# PortiloopV2Altium_Sch.net
KiCad netlist of a schematic drawn in Altium Designer
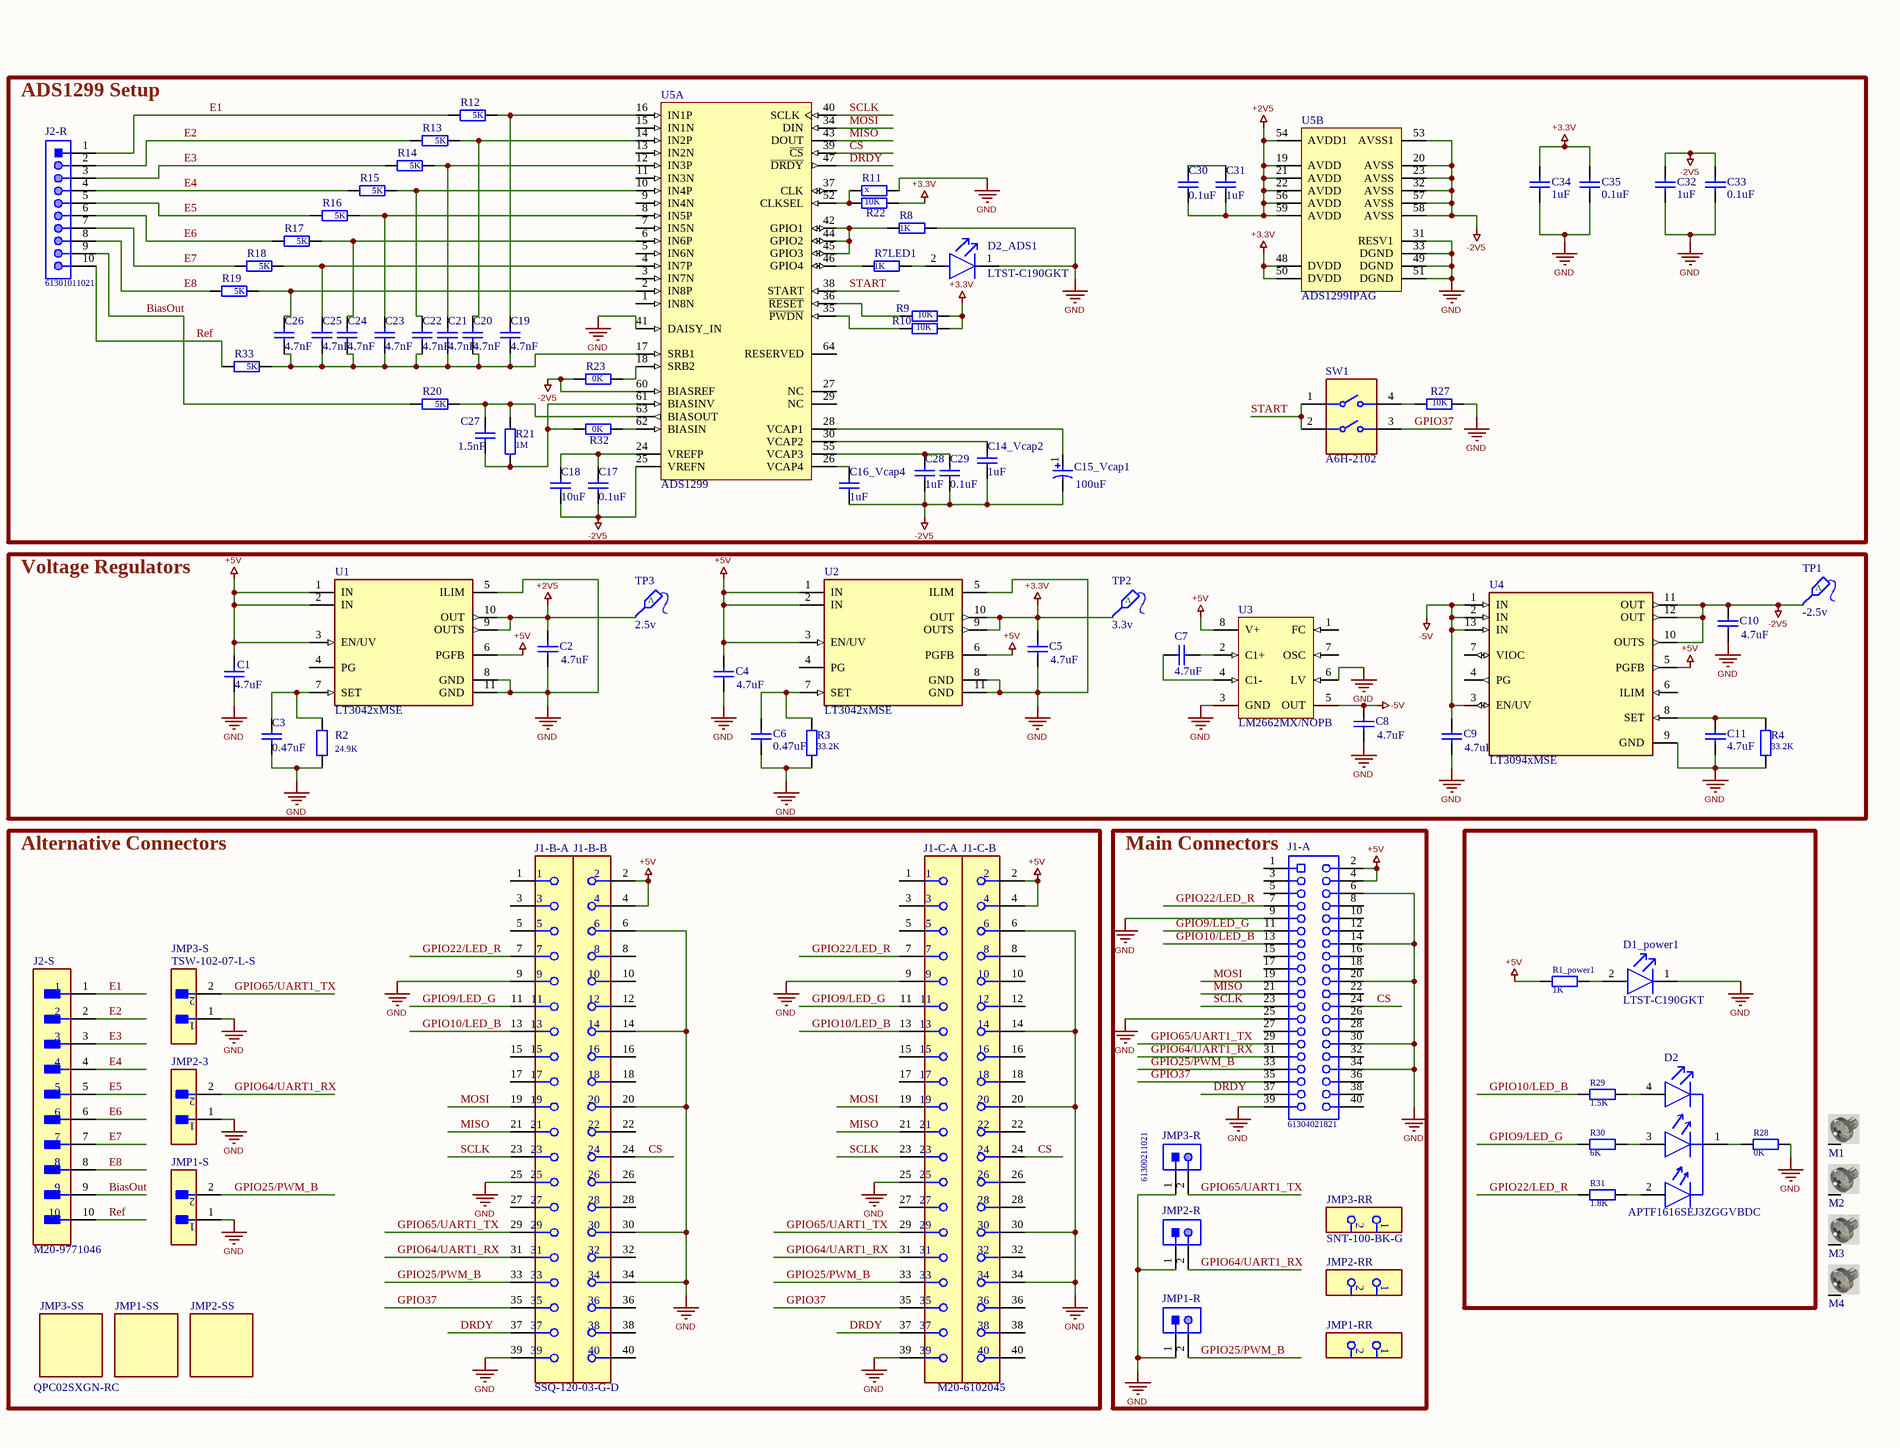
[diagram p0: PortiloopV2Altium_Sch.SchDoc, right]

(export (version "E")
  (design (tool "Eeschema 10.0.6"))
  (components
    (comp (ref "C1")
      (value "4.7uF")
      (footprint "C1206")
      (fields (field (name "Comment") "4.7mkf") (field (name "PUBLISHER") "Altium Limited"))
      (libsource (lib "Miscellaneous Devices") (part "Cap Semi"))
    )
    (comp (ref "C2")
      (value "4.7uF")
      (footprint "C1206")
      (fields (field (name "Comment") "4.7mkf") (field (name "PUBLISHER") "Altium Limited"))
      (libsource (lib "Miscellaneous Devices") (part "Cap Semi"))
    )
    (comp (ref "C3")
      (value "0.47uF")
      (footprint "1608[0603]")
      (fields (field (name "Comment") "0.47mkf") (field (name "PUBLISHER") "Altium Limited"))
      (libsource (lib "Miscellaneous Devices") (part "Cap Semi"))
    )
    (comp (ref "C4")
      (value "4.7uF")
      (footprint "C1206")
      (fields (field (name "Comment") "4.7mkf") (field (name "PUBLISHER") "Altium Limited"))
      (libsource (lib "Miscellaneous Devices") (part "Cap Semi"))
    )
    (comp (ref "C5")
      (value "4.7uF")
      (footprint "C1206")
      (fields (field (name "Comment") "4.7mkf") (field (name "PUBLISHER") "Altium Limited"))
      (libsource (lib "Miscellaneous Devices") (part "Cap Semi"))
    )
    (comp (ref "C6")
      (value "0.47uF")
      (footprint "1608[0603]")
      (fields (field (name "Comment") "0.47mkf") (field (name "PUBLISHER") "Altium Limited"))
      (libsource (lib "Miscellaneous Devices") (part "Cap Semi"))
    )
    (comp (ref "C7")
      (value "4.7uF")
      (footprint "C1206")
      (fields (field (name "Comment") "4.7mkf") (field (name "PUBLISHER") "Altium Limited"))
      (libsource (lib "Miscellaneous Devices") (part "Cap Semi"))
    )
    (comp (ref "C8")
      (value "4.7uF")
      (footprint "C1206")
      (fields (field (name "Comment") "4.7mkf") (field (name "PUBLISHER") "Altium Limited"))
      (libsource (lib "Miscellaneous Devices") (part "Cap Semi"))
    )
    (comp (ref "C9")
      (value "4.7uF")
      (footprint "C1206")
      (fields (field (name "Comment") "4.7mkf") (field (name "PUBLISHER") "Altium Limited"))
      (libsource (lib "Miscellaneous Devices") (part "Cap Semi"))
    )
    (comp (ref "C10")
      (value "4.7uF")
      (footprint "C1206")
      (fields (field (name "Comment") "4.7mkf") (field (name "PUBLISHER") "Altium Limited"))
      (libsource (lib "Miscellaneous Devices") (part "Cap Semi"))
    )
    (comp (ref "C11")
      (value "4.7uF")
      (footprint "C1206")
      (fields (field (name "Comment") "4.7mkf") (field (name "PUBLISHER") "Altium Limited"))
      (libsource (lib "Miscellaneous Devices") (part "Cap Semi"))
    )
    (comp (ref "C14_Vcap2")
      (value "1uF")
      (footprint "1608[0603]")
      (fields (field (name "Comment") "1mkf") (field (name "PUBLISHER") "Altium Limited"))
      (libsource (lib "Miscellaneous Devices") (part "Cap Semi"))
    )
    (comp (ref "C15_Vcap1")
      (value "100mkf")
      (footprint "KEMT-T491-D_M")
      (description "Capacitor, Tantalum, 100 uF, +/- 10%, -55 to 125 degC, 2-Pin SMD, RoHS, Tape and Reel")
      (fields (field (name "TOLERANCE") "20%") (field (name "CAPACITANCE") "100uF"))
      (libsource (lib "Altium Content Vault") (part "CAP-P-2"))
    )
    (comp (ref "C16_Vcap4")
      (value "1uF")
      (footprint "1608[0603]")
      (fields (field (name "Comment") "1mkf") (field (name "PUBLISHER") "Altium Limited"))
      (libsource (lib "Miscellaneous Devices") (part "Cap Semi"))
    )
    (comp (ref "C17")
      (value "0.1uF")
      (footprint "1608[0603]")
      (fields (field (name "Comment") "0.1mkf") (field (name "PUBLISHER") "Altium Limited"))
      (libsource (lib "Miscellaneous Devices") (part "Cap Semi"))
    )
    (comp (ref "C18")
      (value "10uF")
      (footprint "C1206")
      (fields (field (name "Comment") "10mkf") (field (name "PUBLISHER") "Altium Limited"))
      (libsource (lib "Miscellaneous Devices") (part "Cap Semi"))
    )
    (comp (ref "C19")
      (value "4.7nF")
      (footprint "1608[0603]")
      (fields (field (name "Comment") "4.7nf") (field (name "PUBLISHER") "Altium Limited"))
      (libsource (lib "Miscellaneous Devices") (part "Cap Semi"))
    )
    (comp (ref "C20")
      (value "4.7nF")
      (footprint "1608[0603]")
      (fields (field (name "Comment") "4.7nf") (field (name "PUBLISHER") "Altium Limited"))
      (libsource (lib "Miscellaneous Devices") (part "Cap Semi"))
    )
    (comp (ref "C21")
      (value "4.7nF")
      (footprint "1608[0603]")
      (fields (field (name "Comment") "4.7nf") (field (name "PUBLISHER") "Altium Limited"))
      (libsource (lib "Miscellaneous Devices") (part "Cap Semi"))
    )
    (comp (ref "C22")
      (value "4.7nF")
      (footprint "1608[0603]")
      (fields (field (name "Comment") "4.7nf") (field (name "PUBLISHER") "Altium Limited"))
      (libsource (lib "Miscellaneous Devices") (part "Cap Semi"))
    )
    (comp (ref "C23")
      (value "4.7nF")
      (footprint "1608[0603]")
      (fields (field (name "Comment") "4.7nf") (field (name "PUBLISHER") "Altium Limited"))
      (libsource (lib "Miscellaneous Devices") (part "Cap Semi"))
    )
    (comp (ref "C24")
      (value "4.7nF")
      (footprint "1608[0603]")
      (fields (field (name "Comment") "4.7nf") (field (name "PUBLISHER") "Altium Limited"))
      (libsource (lib "Miscellaneous Devices") (part "Cap Semi"))
    )
    (comp (ref "C25")
      (value "4.7nF")
      (footprint "1608[0603]")
      (fields (field (name "Comment") "4.7nf") (field (name "PUBLISHER") "Altium Limited"))
      (libsource (lib "Miscellaneous Devices") (part "Cap Semi"))
    )
    (comp (ref "C26")
      (value "4.7nF")
      (footprint "1608[0603]")
      (fields (field (name "Comment") "4.7nf") (field (name "PUBLISHER") "Altium Limited"))
      (libsource (lib "Miscellaneous Devices") (part "Cap Semi"))
    )
    (comp (ref "C27")
      (value "1.5nF")
      (footprint "1608[0603]")
      (fields (field (name "Comment") "1.5nf") (field (name "PUBLISHER") "Altium Limited"))
      (libsource (lib "Miscellaneous Devices") (part "Cap Semi"))
    )
    (comp (ref "C28")
      (value "1uF")
      (footprint "1608[0603]")
      (fields (field (name "Comment") "1mkf") (field (name "PUBLISHER") "Altium Limited"))
      (libsource (lib "Miscellaneous Devices") (part "Cap Semi"))
    )
    (comp (ref "C29")
      (value "0.1uF")
      (footprint "1608[0603]")
      (fields (field (name "Comment") "0.1mkf") (field (name "PUBLISHER") "Altium Limited"))
      (libsource (lib "Miscellaneous Devices") (part "Cap Semi"))
    )
    (comp (ref "C30")
      (value "0.1uF")
      (footprint "1608[0603]")
      (fields (field (name "Comment") "0.1mkf") (field (name "PUBLISHER") "Altium Limited"))
      (libsource (lib "Miscellaneous Devices") (part "Cap Semi"))
    )
    (comp (ref "C31")
      (value "1uF")
      (footprint "1608[0603]")
      (fields (field (name "Comment") "1mkf") (field (name "PUBLISHER") "Altium Limited"))
      (libsource (lib "Miscellaneous Devices") (part "Cap Semi"))
    )
    (comp (ref "C32")
      (value "1uF")
      (footprint "1608[0603]")
      (fields (field (name "Comment") "1mkf") (field (name "PUBLISHER") "Altium Limited"))
      (libsource (lib "Miscellaneous Devices") (part "Cap Semi"))
    )
    (comp (ref "C33")
      (value "0.1uF")
      (footprint "1608[0603]")
      (fields (field (name "Comment") "0.1mkf") (field (name "PUBLISHER") "Altium Limited"))
      (libsource (lib "Miscellaneous Devices") (part "Cap Semi"))
    )
    (comp (ref "C34")
      (value "1uF")
      (footprint "1608[0603]")
      (fields (field (name "Comment") "1mkf") (field (name "PUBLISHER") "Altium Limited"))
      (libsource (lib "Miscellaneous Devices") (part "Cap Semi"))
    )
    (comp (ref "C35")
      (value "0.1uF")
      (footprint "1608[0603]")
      (fields (field (name "Comment") "0.1mkf") (field (name "PUBLISHER") "Altium Limited"))
      (libsource (lib "Miscellaneous Devices") (part "Cap Semi"))
    )
    (comp (ref "D1_power1")
      (value "LTST-C190GKT")
      (footprint "FP-LTST-C190GKT-MFG")
      (description "LED GREEN CLEAR CHIP SMD")
      (fields (field (name "VOLTAGE") "2V"))
      (libsource (lib "Altium Content Vault") (part "8706943c75ba83719d021d2fdc84c58"))
    )
    (comp (ref "D2")
      (value "APTF1616SEJ3ZGGVBDC")
      (footprint "FP-APTF1616SEJ3ZGGVBDC-MFG")
      (description "LED RGB CLEAR 4SMD")
      (libsource (lib "Altium Content Vault") (part "09016a64638d3f35f69863a61e92420"))
    )
    (comp (ref "D2_ADS1")
      (value "LTST-C190GKT")
      (footprint "FP-LTST-C190GKT-MFG")
      (description "LED GREEN CLEAR CHIP SMD")
      (fields (field (name "VOLTAGE") "2V"))
      (libsource (lib "Altium Content Vault") (part "8706943c75ba83719d021d2fdc84c58"))
    )
    (comp (ref "J1-A")
      (value "61304021821")
      (footprint "61304021821")
      (description "THT Vertical Socket Header WR-PHD, Pitch 2.54 mm, Dual Row, 40 pins")
      (fields (field (name "MANUFACTURER") "Wurth Elektronik") (field (name "PUBLISHER") "WurthElektronik"))
      (libsource (lib "Altium Content Vault") (part "WE-CN-2P-F-R40"))
    )
    (comp (ref "J1-B-")
      (value "SSQ-120-03-G-D")
      (footprint "FP-SSQ-120-03-G-D-MFG")
      (description "CONN RCPT 40POS 0.1 GOLD PCB")
      (libsource (lib "Altium Content Vault") (part "7acf1c4a8db21028d11741a46a6ec78"))
    )
    (comp (ref "J1-C-")
      (value "M20-6102045")
      (footprint "FP-M20-6102045-MFG")
      (description "CONN STKTHRU PC/104 40POS PCB")
      (libsource (lib "Altium Content Vault") (part "7acf1c4a8db21028d11741a46a6ec78"))
    )
    (comp (ref "J2-R")
      (value "61301011021")
      (footprint "61301011021")
      (description "THT Angled Pin Header WR-PHD, Pitch 2.54 mm, Single Row, 10 pins")
      (fields (field (name "MANUFACTURER") "Wurth Elektronik") (field (name "PUBLISHER") "WurthElektronik"))
      (libsource (lib "Altium Content Vault") (part "WE-CN-1P-M-R10"))
    )
    (comp (ref "J2-S")
      (value "M20-9771046")
      (footprint "FP-M20-9771046-MFG")
      (description "CONN HEADER VERT 10POS 2.54MM")
      (libsource (lib "Altium Content Vault") (part "aee40dc8b284c03a16094555aa210be"))
    )
    (comp (ref "JMP1-R")
      (value "61300211021")
      (footprint "61300211021")
      (description "THT Angled Pin Header WR-PHD, Pitch 2.54 mm, Single Row, 2 pins")
      (fields (field (name "MANUFACTURER") "Wurth Elektronik") (field (name "PUBLISHER") "WurthElektronik"))
      (libsource (lib "Altium Content Vault") (part "WE-CN-1P-M-R2"))
    )
    (comp (ref "JMP1-RR")
      (value "SNT-100-BK-G")
      (footprint "FP-SNT-100-BK-G-MFG")
      (description "CONN SHUNT 2POS")
      (libsource (lib "Altium Content Vault") (part "245d4dded57b275ea2dfe9722bb6e84"))
    )
    (comp (ref "JMP1-S")
      (value "TSW-102-07-L-S")
      (footprint "FP-TSW-102-07-L-S-MFG")
      (description "CONN HEADER VERT 2POS 2.54MM")
      (libsource (lib "Altium Content Vault") (part "3bc925449376181038e59eaffc5286c"))
    )
    (comp (ref "JMP1-SS")
      (value "QPC02SXGN-RC")
      (footprint "FP-QPC02SXGN-RC-MFG")
      (description "CONN JUMPER SHORTING .100\" GOLD")
      (fields
        (field (name "MANUFACTURER") "Sullins")
        (field (name "OCTOPART") "https://octopart.com/qpc02sxgn-rc-sullins-19878795")
      )
      (libsource (lib "Altium Content Vault") (part "87292ac8601c6cf2061292f5bede09e"))
    )
    (comp (ref "JMP2-3")
      (value "TSW-102-07-L-S")
      (footprint "FP-TSW-102-07-L-S-MFG")
      (description "CONN HEADER VERT 2POS 2.54MM")
      (libsource (lib "Altium Content Vault") (part "3bc925449376181038e59eaffc5286c"))
    )
    (comp (ref "JMP2-R")
      (value "61300211021")
      (footprint "61300211021")
      (description "THT Angled Pin Header WR-PHD, Pitch 2.54 mm, Single Row, 2 pins")
      (fields (field (name "MANUFACTURER") "Wurth Elektronik") (field (name "PUBLISHER") "WurthElektronik"))
      (libsource (lib "Altium Content Vault") (part "WE-CN-1P-M-R2"))
    )
    (comp (ref "JMP2-RR")
      (value "SNT-100-BK-G")
      (footprint "FP-SNT-100-BK-G-MFG")
      (description "CONN SHUNT 2POS")
      (libsource (lib "Altium Content Vault") (part "245d4dded57b275ea2dfe9722bb6e84"))
    )
    (comp (ref "JMP2-SS")
      (value "QPC02SXGN-RC")
      (footprint "FP-QPC02SXGN-RC-MFG")
      (description "CONN JUMPER SHORTING .100\" GOLD")
      (fields
        (field (name "MANUFACTURER") "Sullins")
        (field (name "OCTOPART") "https://octopart.com/qpc02sxgn-rc-sullins-19878795")
      )
      (libsource (lib "Altium Content Vault") (part "87292ac8601c6cf2061292f5bede09e"))
    )
    (comp (ref "JMP3-R")
      (value "61300211021")
      (footprint "61300211021")
      (description "THT Angled Pin Header WR-PHD, Pitch 2.54 mm, Single Row, 2 pins")
      (fields (field (name "MANUFACTURER") "Wurth Elektronik") (field (name "PUBLISHER") "WurthElektronik"))
      (libsource (lib "Altium Content Vault") (part "WE-CN-1P-M-R2"))
    )
    (comp (ref "JMP3-RR")
      (value "SNT-100-BK-G")
      (footprint "FP-SNT-100-BK-G-MFG")
      (description "CONN SHUNT 2POS")
      (libsource (lib "Altium Content Vault") (part "245d4dded57b275ea2dfe9722bb6e84"))
    )
    (comp (ref "JMP3-S")
      (value "TSW-102-07-L-S")
      (footprint "FP-TSW-102-07-L-S-MFG")
      (description "CONN HEADER VERT 2POS 2.54MM")
      (libsource (lib "Altium Content Vault") (part "3bc925449376181038e59eaffc5286c"))
    )
    (comp (ref "JMP3-SS")
      (value "QPC02SXGN-RC")
      (footprint "FP-QPC02SXGN-RC-MFG")
      (description "CONN JUMPER SHORTING .100\" GOLD")
      (fields
        (field (name "MANUFACTURER") "Sullins")
        (field (name "OCTOPART") "https://octopart.com/qpc02sxgn-rc-sullins-19878795")
      )
      (libsource (lib "Altium Content Vault") (part "87292ac8601c6cf2061292f5bede09e"))
    )
    (comp (ref "M1")
      (value "Screw")
      (footprint "Board Screw_No Silk")
      (description "Board Screw With Spacer")
      (libsource (lib "Lib_marjani") (part "Board Screw"))
    )
    (comp (ref "M2")
      (value "Screw")
      (footprint "Board Screw_No Silk")
      (description "Board Screw With Spacer")
      (libsource (lib "Lib_marjani") (part "Board Screw"))
    )
    (comp (ref "M3")
      (value "Screw")
      (footprint "Board Screw_No Silk")
      (description "Board Screw With Spacer")
      (libsource (lib "Lib_marjani") (part "Board Screw"))
    )
    (comp (ref "M4")
      (value "Screw")
      (footprint "Board Screw_No Silk")
      (description "Board Screw With Spacer")
      (libsource (lib "Lib_marjani") (part "Board Screw"))
    )
    (comp (ref "R1_power1")
      (value "1K")
      (footprint "1608[0603]")
      (description "Resistor")
      (fields (field (name "PUBLISHER") "Altium Limited"))
      (libsource (lib "") (part "Res2_1"))
    )
    (comp (ref "R2")
      (value "24.9K")
      (footprint "1608[0603]")
      (description "Resistor")
      (fields (field (name "PUBLISHER") "Altium Limited"))
      (libsource (lib "") (part "Res2_2"))
    )
    (comp (ref "R3")
      (value "33.2K")
      (footprint "1608[0603]")
      (description "Resistor")
      (fields (field (name "PUBLISHER") "Altium Limited"))
      (libsource (lib "") (part "Res2_2"))
    )
    (comp (ref "R4")
      (value "33.2K")
      (footprint "1608[0603]")
      (description "Resistor")
      (fields (field (name "PUBLISHER") "Altium Limited"))
      (libsource (lib "") (part "Res2_2"))
    )
    (comp (ref "R7LED1")
      (value "1K")
      (footprint "1608[0603]")
      (description "Resistor")
      (fields (field (name "PUBLISHER") "Altium Limited"))
      (libsource (lib "Miscellaneous Devices") (part "Res2"))
    )
    (comp (ref "R8")
      (value "1K")
      (footprint "1608[0603]")
      (description "Resistor")
      (fields (field (name "PUBLISHER") "Altium Limited"))
      (libsource (lib "Miscellaneous Devices") (part "Res2"))
    )
    (comp (ref "R9")
      (value "10K")
      (footprint "1608[0603]")
      (description "Resistor")
      (fields (field (name "PUBLISHER") "Altium Limited"))
      (libsource (lib "") (part "Res2_1"))
    )
    (comp (ref "R10")
      (value "10K")
      (footprint "1608[0603]")
      (description "Resistor")
      (fields (field (name "PUBLISHER") "Altium Limited"))
      (libsource (lib "") (part "Res2_1"))
    )
    (comp (ref "R11")
      (value "x")
      (footprint "1608[0603]")
      (description "Not Connected")
      (fields (field (name "PUBLISHER") "Altium Limited"))
      (libsource (lib "") (part "Res2_1"))
    )
    (comp (ref "R12")
      (value "5K")
      (footprint "1608[0603]")
      (description "Resistor")
      (fields (field (name "PUBLISHER") "Altium Limited"))
      (libsource (lib "Miscellaneous Devices") (part "Res2"))
    )
    (comp (ref "R13")
      (value "5K")
      (footprint "1608[0603]")
      (description "Resistor")
      (fields (field (name "PUBLISHER") "Altium Limited"))
      (libsource (lib "Miscellaneous Devices") (part "Res2"))
    )
    (comp (ref "R14")
      (value "5K")
      (footprint "1608[0603]")
      (description "Resistor")
      (fields (field (name "PUBLISHER") "Altium Limited"))
      (libsource (lib "Miscellaneous Devices") (part "Res2"))
    )
    (comp (ref "R15")
      (value "5K")
      (footprint "1608[0603]")
      (description "Resistor")
      (fields (field (name "PUBLISHER") "Altium Limited"))
      (libsource (lib "Miscellaneous Devices") (part "Res2"))
    )
    (comp (ref "R16")
      (value "5K")
      (footprint "1608[0603]")
      (description "Resistor")
      (fields (field (name "PUBLISHER") "Altium Limited"))
      (libsource (lib "Miscellaneous Devices") (part "Res2"))
    )
    (comp (ref "R17")
      (value "5K")
      (footprint "1608[0603]")
      (description "Resistor")
      (fields (field (name "PUBLISHER") "Altium Limited"))
      (libsource (lib "Miscellaneous Devices") (part "Res2"))
    )
    (comp (ref "R18")
      (value "5K")
      (footprint "1608[0603]")
      (description "Resistor")
      (fields (field (name "PUBLISHER") "Altium Limited"))
      (libsource (lib "Miscellaneous Devices") (part "Res2"))
    )
    (comp (ref "R19")
      (value "5K")
      (footprint "1608[0603]")
      (description "Resistor")
      (fields (field (name "PUBLISHER") "Altium Limited"))
      (libsource (lib "Miscellaneous Devices") (part "Res2"))
    )
    (comp (ref "R20")
      (value "5K")
      (footprint "1608[0603]")
      (description "Resistor")
      (fields (field (name "PUBLISHER") "Altium Limited"))
      (libsource (lib "Miscellaneous Devices") (part "Res2"))
    )
    (comp (ref "R21")
      (value "1M")
      (footprint "1608[0603]")
      (description "Resistor")
      (fields (field (name "PUBLISHER") "Altium Limited"))
      (libsource (lib "") (part "Res2_2"))
    )
    (comp (ref "R22")
      (value "10K")
      (footprint "1608[0603]")
      (description "Resistor")
      (fields (field (name "PUBLISHER") "Altium Limited"))
      (libsource (lib "") (part "Res2_1"))
    )
    (comp (ref "R23")
      (value "0K")
      (footprint "1608[0603]")
      (description "Resistor")
      (fields (field (name "PUBLISHER") "Altium Limited"))
      (libsource (lib "") (part "Res2_1"))
    )
    (comp (ref "R27")
      (value "10K")
      (footprint "1608[0603]")
      (description "Resistor")
      (fields (field (name "PUBLISHER") "Altium Limited"))
      (libsource (lib "") (part "Res2_1"))
    )
    (comp (ref "R28")
      (value "0K")
      (footprint "1608[0603]")
      (description "Resistor")
      (fields (field (name "PUBLISHER") "Altium Limited"))
      (libsource (lib "") (part "Res2_1"))
    )
    (comp (ref "R29")
      (value "1.5K")
      (footprint "1608[0603]")
      (description "Resistor")
      (fields (field (name "PUBLISHER") "Altium Limited"))
      (libsource (lib "") (part "Res2_1"))
    )
    (comp (ref "R30")
      (value "6K")
      (footprint "1608[0603]")
      (description "Resistor")
      (fields (field (name "PUBLISHER") "Altium Limited"))
      (libsource (lib "") (part "Res2_1"))
    )
    (comp (ref "R31")
      (value "1.8K")
      (footprint "1608[0603]")
      (description "Resistor")
      (fields (field (name "PUBLISHER") "Altium Limited"))
      (libsource (lib "") (part "Res2_1"))
    )
    (comp (ref "R32")
      (value "0K")
      (footprint "1608[0603]")
      (description "Resistor")
      (fields (field (name "PUBLISHER") "Altium Limited"))
      (libsource (lib "") (part "Res2_1"))
    )
    (comp (ref "R33")
      (value "5K")
      (footprint "1608[0603]")
      (description "Resistor")
      (fields (field (name "PUBLISHER") "Altium Limited"))
      (libsource (lib "Miscellaneous Devices") (part "Res2"))
    )
    (comp (ref "SW1")
      (value "A6H-2102")
      (footprint "FP-A6H-2102-MFG")
      (description "SWITCH SLIDE DIP SPST 25MA 24V")
      (libsource (lib "Altium Content Vault") (part "070a973bb9dfaf4112c7cb8da95b8f6"))
    )
    (comp (ref "TP1")
      (value "-2.5v")
      (footprint "TESTPOINT1")
      (description "Test Point")
      (libsource (lib "My Library") (part "Test Point"))
    )
    (comp (ref "TP2")
      (value "3.3v")
      (footprint "TESTPOINT1")
      (description "Test Point")
      (libsource (lib "My Library") (part "Test Point"))
    )
    (comp (ref "TP3")
      (value "2.5v")
      (footprint "TESTPOINT1")
      (description "Test Point")
      (libsource (lib "My Library") (part "Test Point"))
    )
    (comp (ref "U1")
      (value "LT3042xMSE")
      (footprint "FP-MSE-10-05-08-1664-IPC_C")
      (description "IC REG LIN POS ADJ 200MA 10MSOP")
      (libsource (lib "Altium Content Vault") (part "617b45537435f4b0c995ef5898f6a34"))
    )
    (comp (ref "U2")
      (value "LT3042xMSE")
      (footprint "FP-MSE-10-05-08-1664-IPC_C")
      (description "IC REG LIN POS ADJ 200MA 10MSOP")
      (libsource (lib "Altium Content Vault") (part "617b45537435f4b0c995ef5898f6a34"))
    )
    (comp (ref "U3")
      (value "LM2662MX/NOPB")
      (footprint "D0008A_M")
      (description "Switched Capacitor Voltage Converter, 8-pin Narrow SOIC, Pb-Free")
      (fields (field (name "MANUFACTURER") "Texas Instruments"))
      (libsource (lib "Altium Content Vault") (part "PM-CHP-LM2660M-8"))
    )
    (comp (ref "U4")
      (value "LT3094xMSE")
      (footprint "FP-MSE-12-05-08-1666-IPC_A")
      (description "IC REG LIN NEG ADJ 500MA 12MSOP")
      (libsource (lib "Altium Content Vault") (part "4f09b0e52ede19156f7e08ace673db3"))
    )
    (comp (ref "U5")
      (value "ADS1299IPAG")
      (footprint "PAG0064A_M")
      (fields (field (name "MANUFACTURER") "Texas Instruments") (field (name "PARTNUMBER") "ADS1299IPAG"))
      (libsource (lib "Altium Content Vault") (part "TI-ADS1299-PAG-64"))
    )
  )
  (nets
    (net (code "1") (name "+2V5") (class "Default")
      (node (ref "C2") (pin "2") (pinfunction "2_2") (pintype "passive"))
      (node (ref "C30") (pin "2") (pinfunction "2_2") (pintype "passive"))
      (node (ref "C31") (pin "2") (pinfunction "2_2") (pintype "passive"))
      (node (ref "TP3") (pin "1") (pinfunction "T_1") (pintype "passive"))
      (node (ref "U1") (pin "10") (pinfunction "OUT_10") (pintype "output"))
      (node (ref "U1") (pin "9") (pinfunction "OUTS_9") (pintype "output"))
      (node (ref "U5") (pin "19") (pinfunction "AVDD_19") (pintype "power_in"))
      (node (ref "U5") (pin "21") (pinfunction "AVDD_21") (pintype "power_in"))
      (node (ref "U5") (pin "22") (pinfunction "AVDD_22") (pintype "power_in"))
      (node (ref "U5") (pin "54") (pinfunction "AVDD1_54") (pintype "power_in"))
      (node (ref "U5") (pin "56") (pinfunction "AVDD_56") (pintype "power_in"))
      (node (ref "U5") (pin "59") (pinfunction "AVDD_59") (pintype "power_in"))
    )
    (net (code "2") (name "+3.3V") (class "Default")
      (node (ref "C34") (pin "2") (pinfunction "2_2") (pintype "passive"))
      (node (ref "C35") (pin "2") (pinfunction "2_2") (pintype "passive"))
      (node (ref "C5") (pin "2") (pinfunction "2_2") (pintype "passive"))
      (node (ref "R10") (pin "1") (pinfunction "1_1") (pintype "passive"))
      (node (ref "R22") (pin "1") (pinfunction "1_1") (pintype "passive"))
      (node (ref "R9") (pin "1") (pinfunction "1_1") (pintype "passive"))
      (node (ref "TP2") (pin "1") (pinfunction "T_1") (pintype "passive"))
      (node (ref "U2") (pin "10") (pinfunction "OUT_10") (pintype "output"))
      (node (ref "U2") (pin "9") (pinfunction "OUTS_9") (pintype "output"))
      (node (ref "U5") (pin "48") (pinfunction "DVDD_48") (pintype "power_in"))
      (node (ref "U5") (pin "50") (pinfunction "DVDD_50") (pintype "power_in"))
    )
    (net (code "3") (name "+5V") (class "Default")
      (node (ref "C1") (pin "2") (pinfunction "2_2") (pintype "passive"))
      (node (ref "C4") (pin "2") (pinfunction "2_2") (pintype "passive"))
      (node (ref "J1-A") (pin "2") (pinfunction "2_2") (pintype "passive"))
      (node (ref "J1-A") (pin "4") (pinfunction "4_4") (pintype "passive"))
      (node (ref "J1-B-") (pin "2") (pinfunction "2_2") (pintype "passive"))
      (node (ref "J1-B-") (pin "4") (pinfunction "4_4") (pintype "passive"))
      (node (ref "J1-C-") (pin "2") (pinfunction "2_2") (pintype "passive"))
      (node (ref "J1-C-") (pin "4") (pinfunction "4_4") (pintype "passive"))
      (node (ref "R1_power1") (pin "2") (pinfunction "2_2") (pintype "passive"))
      (node (ref "U1") (pin "1") (pinfunction "IN_1") (pintype "power_in"))
      (node (ref "U1") (pin "2") (pinfunction "IN_2") (pintype "power_in"))
      (node (ref "U1") (pin "3") (pinfunction "EN/UV_3") (pintype "input"))
      (node (ref "U1") (pin "6") (pinfunction "PGFB_6") (pintype "passive"))
      (node (ref "U2") (pin "1") (pinfunction "IN_1") (pintype "power_in"))
      (node (ref "U2") (pin "2") (pinfunction "IN_2") (pintype "power_in"))
      (node (ref "U2") (pin "3") (pinfunction "EN/UV_3") (pintype "input"))
      (node (ref "U2") (pin "6") (pinfunction "PGFB_6") (pintype "passive"))
      (node (ref "U3") (pin "8") (pinfunction "V+_8") (pintype "power_in"))
      (node (ref "U4") (pin "5") (pinfunction "PGFB_5") (pintype "output"))
    )
    (net (code "4") (name "-2V5") (class "Default")
      (node (ref "C10") (pin "2") (pinfunction "2_2") (pintype "passive"))
      (node (ref "C14_Vcap2") (pin "1") (pinfunction "1_1") (pintype "passive"))
      (node (ref "C15_Vcap1") (pin "2") (pinfunction "2_2") (pintype "passive"))
      (node (ref "C16_Vcap4") (pin "1") (pinfunction "1_1") (pintype "passive"))
      (node (ref "C17") (pin "2") (pinfunction "2_2") (pintype "passive"))
      (node (ref "C18") (pin "1") (pinfunction "1_1") (pintype "passive"))
      (node (ref "C28") (pin "1") (pinfunction "1_1") (pintype "passive"))
      (node (ref "C29") (pin "1") (pinfunction "1_1") (pintype "passive"))
      (node (ref "C32") (pin "2") (pinfunction "2_2") (pintype "passive"))
      (node (ref "C33") (pin "2") (pinfunction "2_2") (pintype "passive"))
      (node (ref "R23") (pin "2") (pinfunction "2_2") (pintype "passive"))
      (node (ref "TP1") (pin "1") (pinfunction "T_1") (pintype "passive"))
      (node (ref "U4") (pin "10") (pinfunction "OUTS_10") (pintype "output"))
      (node (ref "U4") (pin "11") (pinfunction "OUT_11") (pintype "output"))
      (node (ref "U4") (pin "12") (pinfunction "OUT_12") (pintype "output"))
      (node (ref "U5") (pin "20") (pinfunction "AVSS_20") (pintype "power_in"))
      (node (ref "U5") (pin "23") (pinfunction "AVSS_23") (pintype "power_in"))
      (node (ref "U5") (pin "25") (pinfunction "VREFN_25") (pintype "passive"))
      (node (ref "U5") (pin "32") (pinfunction "AVSS_32") (pintype "power_in"))
      (node (ref "U5") (pin "53") (pinfunction "AVSS1_53") (pintype "power_in"))
      (node (ref "U5") (pin "57") (pinfunction "AVSS_57") (pintype "power_in"))
      (node (ref "U5") (pin "58") (pinfunction "AVSS_58") (pintype "power_in"))
      (node (ref "U5") (pin "60") (pinfunction "BIASREF_60") (pintype "input"))
    )
    (net (code "5") (name "-5V") (class "Default")
      (node (ref "C8") (pin "2") (pinfunction "2_2") (pintype "passive"))
      (node (ref "C9") (pin "2") (pinfunction "2_2") (pintype "passive"))
      (node (ref "U3") (pin "5") (pinfunction "OUT_5") (pintype "power_in"))
      (node (ref "U4") (pin "1") (pinfunction "IN_1") (pintype "input"))
      (node (ref "U4") (pin "13") (pinfunction "IN_13") (pintype "input"))
      (node (ref "U4") (pin "2") (pinfunction "IN_2") (pintype "input"))
      (node (ref "U4") (pin "3") (pinfunction "EN/UV_3") (pintype "bidirectional"))
    )
    (net (code "6") (name "/BiasOut") (class "Default")
      (node (ref "J2-R") (pin "9") (pinfunction "9_9") (pintype "passive"))
      (node (ref "J2-S") (pin "9") (pinfunction "9_9") (pintype "passive"))
      (node (ref "R20") (pin "1") (pinfunction "1_1") (pintype "passive"))
    )
    (net (code "7") (name "/CS") (class "Default")
      (node (ref "J1-A") (pin "24") (pinfunction "24_24") (pintype "passive"))
      (node (ref "J1-B-") (pin "24") (pinfunction "24_24") (pintype "passive"))
      (node (ref "J1-C-") (pin "24") (pinfunction "24_24") (pintype "passive"))
      (node (ref "U5") (pin "39") (pinfunction "~{CS}_39") (pintype "input"))
    )
    (net (code "8") (name "/DRDY") (class "Default")
      (node (ref "J1-A") (pin "37") (pinfunction "37_37") (pintype "passive"))
      (node (ref "J1-B-") (pin "37") (pinfunction "37_37") (pintype "passive"))
      (node (ref "J1-C-") (pin "37") (pinfunction "37_37") (pintype "passive"))
      (node (ref "U5") (pin "47") (pinfunction "~{DRDY}_47") (pintype "output"))
    )
    (net (code "9") (name "/E1") (class "Default")
      (node (ref "J2-R") (pin "1") (pinfunction "1_1") (pintype "passive"))
      (node (ref "J2-S") (pin "1") (pinfunction "1_1") (pintype "passive"))
      (node (ref "R12") (pin "1") (pinfunction "1_1") (pintype "passive"))
    )
    (net (code "10") (name "/E2") (class "Default")
      (node (ref "J2-R") (pin "2") (pinfunction "2_2") (pintype "passive"))
      (node (ref "J2-S") (pin "2") (pinfunction "2_2") (pintype "passive"))
      (node (ref "R13") (pin "1") (pinfunction "1_1") (pintype "passive"))
    )
    (net (code "11") (name "/E3") (class "Default")
      (node (ref "J2-R") (pin "3") (pinfunction "3_3") (pintype "passive"))
      (node (ref "J2-S") (pin "3") (pinfunction "3_3") (pintype "passive"))
      (node (ref "R14") (pin "1") (pinfunction "1_1") (pintype "passive"))
    )
    (net (code "12") (name "/E4") (class "Default")
      (node (ref "J2-R") (pin "4") (pinfunction "4_4") (pintype "passive"))
      (node (ref "J2-S") (pin "4") (pinfunction "4_4") (pintype "passive"))
      (node (ref "R15") (pin "1") (pinfunction "1_1") (pintype "passive"))
    )
    (net (code "13") (name "/E5") (class "Default")
      (node (ref "J2-R") (pin "5") (pinfunction "5_5") (pintype "passive"))
      (node (ref "J2-S") (pin "5") (pinfunction "5_5") (pintype "passive"))
      (node (ref "R16") (pin "1") (pinfunction "1_1") (pintype "passive"))
    )
    (net (code "14") (name "/E6") (class "Default")
      (node (ref "J2-R") (pin "6") (pinfunction "6_6") (pintype "passive"))
      (node (ref "J2-S") (pin "6") (pinfunction "6_6") (pintype "passive"))
      (node (ref "R17") (pin "1") (pinfunction "1_1") (pintype "passive"))
    )
    (net (code "15") (name "/E7") (class "Default")
      (node (ref "J2-R") (pin "7") (pinfunction "7_7") (pintype "passive"))
      (node (ref "J2-S") (pin "7") (pinfunction "7_7") (pintype "passive"))
      (node (ref "R18") (pin "1") (pinfunction "1_1") (pintype "passive"))
    )
    (net (code "16") (name "/E8") (class "Default")
      (node (ref "J2-R") (pin "8") (pinfunction "8_8") (pintype "passive"))
      (node (ref "J2-S") (pin "8") (pinfunction "8_8") (pintype "passive"))
      (node (ref "R19") (pin "1") (pinfunction "1_1") (pintype "passive"))
    )
    (net (code "17") (name "/GPIO9{slash}LED_G") (class "Default")
      (node (ref "J1-A") (pin "11") (pinfunction "11_11") (pintype "passive"))
      (node (ref "J1-B-") (pin "11") (pinfunction "11_11") (pintype "passive"))
      (node (ref "J1-C-") (pin "11") (pinfunction "11_11") (pintype "passive"))
      (node (ref "R30") (pin "2") (pinfunction "2_2") (pintype "passive"))
    )
    (net (code "18") (name "/GPIO10{slash}LED_B") (class "Default")
      (node (ref "J1-A") (pin "13") (pinfunction "13_13") (pintype "passive"))
      (node (ref "J1-B-") (pin "13") (pinfunction "13_13") (pintype "passive"))
      (node (ref "J1-C-") (pin "13") (pinfunction "13_13") (pintype "passive"))
      (node (ref "R29") (pin "2") (pinfunction "2_2") (pintype "passive"))
    )
    (net (code "19") (name "/GPIO22{slash}LED_R") (class "Default")
      (node (ref "J1-A") (pin "7") (pinfunction "7_7") (pintype "passive"))
      (node (ref "J1-B-") (pin "7") (pinfunction "7_7") (pintype "passive"))
      (node (ref "J1-C-") (pin "7") (pinfunction "7_7") (pintype "passive"))
      (node (ref "R31") (pin "2") (pinfunction "2_2") (pintype "passive"))
    )
    (net (code "20") (name "/GPIO25{slash}PWM_B") (class "Default")
      (node (ref "J1-A") (pin "33") (pinfunction "33_33") (pintype "passive"))
      (node (ref "J1-B-") (pin "33") (pinfunction "33_33") (pintype "passive"))
      (node (ref "J1-C-") (pin "33") (pinfunction "33_33") (pintype "passive"))
      (node (ref "JMP1-R") (pin "2") (pinfunction "2_2") (pintype "passive"))
      (node (ref "JMP1-S") (pin "2") (pinfunction "2_2") (pintype "passive"))
    )
    (net (code "21") (name "/GPIO37") (class "Default")
      (node (ref "J1-A") (pin "35") (pinfunction "35_35") (pintype "passive"))
      (node (ref "J1-B-") (pin "35") (pinfunction "35_35") (pintype "passive"))
      (node (ref "J1-C-") (pin "35") (pinfunction "35_35") (pintype "passive"))
      (node (ref "SW1") (pin "3") (pinfunction "3_3") (pintype "passive"))
    )
    (net (code "22") (name "/GPIO64{slash}UART1_RX") (class "Default")
      (node (ref "J1-A") (pin "31") (pinfunction "31_31") (pintype "passive"))
      (node (ref "J1-B-") (pin "31") (pinfunction "31_31") (pintype "passive"))
      (node (ref "J1-C-") (pin "31") (pinfunction "31_31") (pintype "passive"))
      (node (ref "JMP2-3") (pin "2") (pinfunction "2_2") (pintype "passive"))
      (node (ref "JMP2-R") (pin "2") (pinfunction "2_2") (pintype "passive"))
    )
    (net (code "23") (name "/GPIO65{slash}UART1_TX") (class "Default")
      (node (ref "J1-A") (pin "29") (pinfunction "29_29") (pintype "passive"))
      (node (ref "J1-B-") (pin "29") (pinfunction "29_29") (pintype "passive"))
      (node (ref "J1-C-") (pin "29") (pinfunction "29_29") (pintype "passive"))
      (node (ref "JMP3-R") (pin "2") (pinfunction "2_2") (pintype "passive"))
      (node (ref "JMP3-S") (pin "2") (pinfunction "2_2") (pintype "passive"))
    )
    (net (code "24") (name "/MISO") (class "Default")
      (node (ref "J1-A") (pin "21") (pinfunction "21_21") (pintype "passive"))
      (node (ref "J1-B-") (pin "21") (pinfunction "21_21") (pintype "passive"))
      (node (ref "J1-C-") (pin "21") (pinfunction "21_21") (pintype "passive"))
      (node (ref "U5") (pin "43") (pinfunction "DOUT_43") (pintype "tri_state"))
    )
    (net (code "25") (name "/MOSI") (class "Default")
      (node (ref "J1-A") (pin "19") (pinfunction "19_19") (pintype "passive"))
      (node (ref "J1-B-") (pin "19") (pinfunction "19_19") (pintype "passive"))
      (node (ref "J1-C-") (pin "19") (pinfunction "19_19") (pintype "passive"))
      (node (ref "U5") (pin "34") (pinfunction "DIN_34") (pintype "input"))
    )
    (net (code "26") (name "/Ref") (class "Default")
      (node (ref "J2-R") (pin "10") (pinfunction "10_10") (pintype "passive"))
      (node (ref "J2-S") (pin "10") (pinfunction "10_10") (pintype "passive"))
      (node (ref "R33") (pin "1") (pinfunction "1_1") (pintype "passive"))
    )
    (net (code "27") (name "/SCLK") (class "Default")
      (node (ref "J1-A") (pin "23") (pinfunction "23_23") (pintype "passive"))
      (node (ref "J1-B-") (pin "23") (pinfunction "23_23") (pintype "passive"))
      (node (ref "J1-C-") (pin "23") (pinfunction "23_23") (pintype "passive"))
      (node (ref "U5") (pin "40") (pinfunction "SCLK_40") (pintype "input"))
    )
    (net (code "28") (name "/START") (class "Default")
      (node (ref "SW1") (pin "1") (pinfunction "1_1") (pintype "passive"))
      (node (ref "SW1") (pin "2") (pinfunction "2_2") (pintype "passive"))
      (node (ref "U5") (pin "38") (pinfunction "START_38") (pintype "input"))
    )
    (net (code "29") (name "GND") (class "Default")
      (node (ref "C1") (pin "1") (pinfunction "1_1") (pintype "passive"))
      (node (ref "C10") (pin "1") (pinfunction "1_1") (pintype "passive"))
      (node (ref "C11") (pin "1") (pinfunction "1_1") (pintype "passive"))
      (node (ref "C2") (pin "1") (pinfunction "1_1") (pintype "passive"))
      (node (ref "C3") (pin "1") (pinfunction "1_1") (pintype "passive"))
      (node (ref "C32") (pin "1") (pinfunction "1_1") (pintype "passive"))
      (node (ref "C33") (pin "1") (pinfunction "1_1") (pintype "passive"))
      (node (ref "C34") (pin "1") (pinfunction "1_1") (pintype "passive"))
      (node (ref "C35") (pin "1") (pinfunction "1_1") (pintype "passive"))
      (node (ref "C4") (pin "1") (pinfunction "1_1") (pintype "passive"))
      (node (ref "C5") (pin "1") (pinfunction "1_1") (pintype "passive"))
      (node (ref "C6") (pin "2") (pinfunction "2_2") (pintype "passive"))
      (node (ref "C8") (pin "1") (pinfunction "1_1") (pintype "passive"))
      (node (ref "C9") (pin "1") (pinfunction "1_1") (pintype "passive"))
      (node (ref "D1_power1") (pin "1") (pinfunction "C_1") (pintype "passive"))
      (node (ref "D2_ADS1") (pin "1") (pinfunction "C_1") (pintype "passive"))
      (node (ref "J1-A") (pin "14") (pinfunction "14_14") (pintype "passive"))
      (node (ref "J1-A") (pin "20") (pinfunction "20_20") (pintype "passive"))
      (node (ref "J1-A") (pin "25") (pinfunction "25_25") (pintype "passive"))
      (node (ref "J1-A") (pin "30") (pinfunction "30_30") (pintype "passive"))
      (node (ref "J1-A") (pin "34") (pinfunction "34_34") (pintype "passive"))
      (node (ref "J1-A") (pin "39") (pinfunction "39_39") (pintype "passive"))
      (node (ref "J1-A") (pin "6") (pinfunction "6_6") (pintype "passive"))
      (node (ref "J1-A") (pin "9") (pinfunction "9_9") (pintype "passive"))
      (node (ref "J1-B-") (pin "14") (pinfunction "14_14") (pintype "passive"))
      (node (ref "J1-B-") (pin "20") (pinfunction "20_20") (pintype "passive"))
      (node (ref "J1-B-") (pin "25") (pinfunction "25_25") (pintype "passive"))
      (node (ref "J1-B-") (pin "30") (pinfunction "30_30") (pintype "passive"))
      (node (ref "J1-B-") (pin "34") (pinfunction "34_34") (pintype "passive"))
      (node (ref "J1-B-") (pin "39") (pinfunction "39_39") (pintype "passive"))
      (node (ref "J1-B-") (pin "6") (pinfunction "6_6") (pintype "passive"))
      (node (ref "J1-B-") (pin "9") (pinfunction "9_9") (pintype "passive"))
      (node (ref "J1-C-") (pin "14") (pinfunction "14_14") (pintype "passive"))
      (node (ref "J1-C-") (pin "20") (pinfunction "20_20") (pintype "passive"))
      (node (ref "J1-C-") (pin "25") (pinfunction "25_25") (pintype "passive"))
      (node (ref "J1-C-") (pin "30") (pinfunction "30_30") (pintype "passive"))
      (node (ref "J1-C-") (pin "34") (pinfunction "34_34") (pintype "passive"))
      (node (ref "J1-C-") (pin "39") (pinfunction "39_39") (pintype "passive"))
      (node (ref "J1-C-") (pin "6") (pinfunction "6_6") (pintype "passive"))
      (node (ref "J1-C-") (pin "9") (pinfunction "9_9") (pintype "passive"))
      (node (ref "JMP1-R") (pin "1") (pinfunction "1_1") (pintype "passive"))
      (node (ref "JMP1-S") (pin "1") (pinfunction "1_1") (pintype "passive"))
      (node (ref "JMP2-3") (pin "1") (pinfunction "1_1") (pintype "passive"))
      (node (ref "JMP2-R") (pin "1") (pinfunction "1_1") (pintype "passive"))
      (node (ref "JMP3-R") (pin "1") (pinfunction "1_1") (pintype "passive"))
      (node (ref "JMP3-S") (pin "1") (pinfunction "1_1") (pintype "passive"))
      (node (ref "R11") (pin "1") (pinfunction "1_1") (pintype "passive"))
      (node (ref "R2") (pin "2") (pinfunction "2_2") (pintype "passive"))
      (node (ref "R27") (pin "1") (pinfunction "1_1") (pintype "passive"))
      (node (ref "R28") (pin "1") (pinfunction "1_1") (pintype "passive"))
      (node (ref "R3") (pin "2") (pinfunction "2_2") (pintype "passive"))
      (node (ref "R4") (pin "2") (pinfunction "2_2") (pintype "passive"))
      (node (ref "R8") (pin "2") (pinfunction "2_2") (pintype "passive"))
      (node (ref "U1") (pin "11") (pinfunction "GND_11") (pintype "power_in"))
      (node (ref "U1") (pin "5") (pinfunction "ILIM_5") (pintype "passive"))
      (node (ref "U1") (pin "8") (pinfunction "GND_8") (pintype "open_emitter"))
      (node (ref "U2") (pin "11") (pinfunction "GND_11") (pintype "power_in"))
      (node (ref "U2") (pin "5") (pinfunction "ILIM_5") (pintype "passive"))
      (node (ref "U2") (pin "8") (pinfunction "GND_8") (pintype "open_emitter"))
      (node (ref "U3") (pin "3") (pinfunction "GND_3") (pintype "power_in"))
      (node (ref "U3") (pin "6") (pinfunction "LV_6") (pintype "input"))
      (node (ref "U4") (pin "9") (pinfunction "GND_9") (pintype "power_in"))
      (node (ref "U5") (pin "31") (pinfunction "RESV1_31") (pintype "power_in"))
      (node (ref "U5") (pin "33") (pinfunction "DGND_33") (pintype "power_in"))
      (node (ref "U5") (pin "41") (pinfunction "DAISY_IN_41") (pintype "input"))
      (node (ref "U5") (pin "49") (pinfunction "DGND_49") (pintype "power_in"))
      (node (ref "U5") (pin "51") (pinfunction "DGND_51") (pintype "power_in"))
    )
    (net (code "30") (name "Net-(C30-Pad1)") (class "Default")
      (node (ref "C30") (pin "1") (pinfunction "1_1") (pintype "passive"))
      (node (ref "C31") (pin "1") (pinfunction "1_1") (pintype "passive"))
    )
    (net (code "31") (name "Net-(D1_power1-A)") (class "Default")
      (node (ref "D1_power1") (pin "2") (pinfunction "A_2") (pintype "passive"))
      (node (ref "R1_power1") (pin "1") (pinfunction "1_1") (pintype "passive"))
    )
    (net (code "32") (name "Net-(D2-BLUE_A)") (class "Default")
      (node (ref "D2") (pin "4") (pinfunction "BLUE_A_4") (pintype "passive"))
      (node (ref "R29") (pin "1") (pinfunction "1_1") (pintype "passive"))
    )
    (net (code "33") (name "Net-(D2-COMMON_CATHODE)") (class "Default")
      (node (ref "D2") (pin "1") (pinfunction "COMMON_CATHODE_1") (pintype "passive"))
      (node (ref "R28") (pin "2") (pinfunction "2_2") (pintype "passive"))
    )
    (net (code "34") (name "Net-(D2-GREEN_A)") (class "Default")
      (node (ref "D2") (pin "3") (pinfunction "GREEN_A_3") (pintype "passive"))
      (node (ref "R30") (pin "1") (pinfunction "1_1") (pintype "passive"))
    )
    (net (code "35") (name "Net-(D2-RED_A)") (class "Default")
      (node (ref "D2") (pin "2") (pinfunction "RED_A_2") (pintype "passive"))
      (node (ref "R31") (pin "1") (pinfunction "1_1") (pintype "passive"))
    )
    (net (code "36") (name "Net-(D2_ADS1-A)") (class "Default")
      (node (ref "D2_ADS1") (pin "2") (pinfunction "A_2") (pintype "passive"))
      (node (ref "R7LED1") (pin "2") (pinfunction "2_2") (pintype "passive"))
    )
    (net (code "37") (name "Net-(R27-Pad2)") (class "Default")
      (node (ref "R27") (pin "2") (pinfunction "2_2") (pintype "passive"))
      (node (ref "SW1") (pin "4") (pinfunction "4_4") (pintype "passive"))
    )
    (net (code "38") (name "Net-(U1-SET)") (class "Default")
      (node (ref "C3") (pin "2") (pinfunction "2_2") (pintype "passive"))
      (node (ref "R2") (pin "1") (pinfunction "1_1") (pintype "passive"))
      (node (ref "U1") (pin "7") (pinfunction "SET_7") (pintype "input"))
    )
    (net (code "39") (name "Net-(U2-SET)") (class "Default")
      (node (ref "C6") (pin "1") (pinfunction "1_1") (pintype "passive"))
      (node (ref "R3") (pin "1") (pinfunction "1_1") (pintype "passive"))
      (node (ref "U2") (pin "7") (pinfunction "SET_7") (pintype "input"))
    )
    (net (code "40") (name "Net-(U3-C1+)") (class "Default")
      (node (ref "C7") (pin "2") (pinfunction "2_2") (pintype "passive"))
      (node (ref "U3") (pin "2") (pinfunction "C1+_2") (pintype "input"))
    )
    (net (code "41") (name "Net-(U3-C1-)") (class "Default")
      (node (ref "C7") (pin "1") (pinfunction "1_1") (pintype "passive"))
      (node (ref "U3") (pin "4") (pinfunction "C1-_4") (pintype "input"))
    )
    (net (code "42") (name "Net-(U4-SET)") (class "Default")
      (node (ref "C11") (pin "2") (pinfunction "2_2") (pintype "passive"))
      (node (ref "R4") (pin "1") (pinfunction "1_1") (pintype "passive"))
      (node (ref "U4") (pin "8") (pinfunction "SET_8") (pintype "input"))
    )
    (net (code "43") (name "Net-(U5A-BIASIN)") (class "Default")
      (node (ref "R32") (pin "1") (pinfunction "1_1") (pintype "passive"))
      (node (ref "U5") (pin "62") (pinfunction "BIASIN_62") (pintype "input"))
    )
    (net (code "44") (name "Net-(U5A-BIASINV)") (class "Default")
      (node (ref "C27") (pin "1") (pinfunction "1_1") (pintype "passive"))
      (node (ref "R21") (pin "2") (pinfunction "2_2") (pintype "passive"))
      (node (ref "R32") (pin "2") (pinfunction "2_2") (pintype "passive"))
      (node (ref "U5") (pin "61") (pinfunction "BIASINV_61") (pintype "input"))
    )
    (net (code "45") (name "Net-(U5A-BIASOUT)") (class "Default")
      (node (ref "C27") (pin "2") (pinfunction "2_2") (pintype "passive"))
      (node (ref "R20") (pin "2") (pinfunction "2_2") (pintype "passive"))
      (node (ref "R21") (pin "1") (pinfunction "1_1") (pintype "passive"))
      (node (ref "U5") (pin "63") (pinfunction "BIASOUT_63") (pintype "output"))
    )
    (net (code "46") (name "Net-(U5A-CLKSEL)") (class "Default")
      (node (ref "R11") (pin "2") (pinfunction "2_2") (pintype "passive"))
      (node (ref "R22") (pin "2") (pinfunction "2_2") (pintype "passive"))
      (node (ref "U5") (pin "52") (pinfunction "CLKSEL_52") (pintype "input"))
    )
    (net (code "47") (name "Net-(U5A-GPIO1)") (class "Default")
      (node (ref "R8") (pin "1") (pinfunction "1_1") (pintype "passive"))
      (node (ref "U5") (pin "42") (pinfunction "GPIO1_42") (pintype "bidirectional"))
      (node (ref "U5") (pin "44") (pinfunction "GPIO2_44") (pintype "bidirectional"))
      (node (ref "U5") (pin "45") (pinfunction "GPIO3_45") (pintype "bidirectional"))
    )
    (net (code "48") (name "Net-(U5A-GPIO4)") (class "Default")
      (node (ref "R7LED1") (pin "1") (pinfunction "1_1") (pintype "passive"))
      (node (ref "U5") (pin "46") (pinfunction "GPIO4_46") (pintype "bidirectional"))
    )
    (net (code "49") (name "Net-(U5A-IN1P)") (class "Default")
      (node (ref "C19") (pin "2") (pinfunction "2_2") (pintype "passive"))
      (node (ref "R12") (pin "2") (pinfunction "2_2") (pintype "passive"))
      (node (ref "U5") (pin "16") (pinfunction "IN1P_16") (pintype "input"))
    )
    (net (code "50") (name "Net-(U5A-IN2P)") (class "Default")
      (node (ref "C20") (pin "2") (pinfunction "2_2") (pintype "passive"))
      (node (ref "R13") (pin "2") (pinfunction "2_2") (pintype "passive"))
      (node (ref "U5") (pin "14") (pinfunction "IN2P_14") (pintype "input"))
    )
    (net (code "51") (name "Net-(U5A-IN3P)") (class "Default")
      (node (ref "C21") (pin "2") (pinfunction "2_2") (pintype "passive"))
      (node (ref "R14") (pin "2") (pinfunction "2_2") (pintype "passive"))
      (node (ref "U5") (pin "12") (pinfunction "IN3P_12") (pintype "input"))
    )
    (net (code "52") (name "Net-(U5A-IN4P)") (class "Default")
      (node (ref "C22") (pin "2") (pinfunction "2_2") (pintype "passive"))
      (node (ref "R15") (pin "2") (pinfunction "2_2") (pintype "passive"))
      (node (ref "U5") (pin "10") (pinfunction "IN4P_10") (pintype "input"))
    )
    (net (code "53") (name "Net-(U5A-IN5P)") (class "Default")
      (node (ref "C23") (pin "2") (pinfunction "2_2") (pintype "passive"))
      (node (ref "R16") (pin "2") (pinfunction "2_2") (pintype "passive"))
      (node (ref "U5") (pin "8") (pinfunction "IN5P_8") (pintype "input"))
    )
    (net (code "54") (name "Net-(U5A-IN6P)") (class "Default")
      (node (ref "C24") (pin "2") (pinfunction "2_2") (pintype "passive"))
      (node (ref "R17") (pin "2") (pinfunction "2_2") (pintype "passive"))
      (node (ref "U5") (pin "6") (pinfunction "IN6P_6") (pintype "input"))
    )
    (net (code "55") (name "Net-(U5A-IN7P)") (class "Default")
      (node (ref "C25") (pin "2") (pinfunction "2_2") (pintype "passive"))
      (node (ref "R18") (pin "2") (pinfunction "2_2") (pintype "passive"))
      (node (ref "U5") (pin "4") (pinfunction "IN7P_4") (pintype "input"))
    )
    (net (code "56") (name "Net-(U5A-IN8P)") (class "Default")
      (node (ref "C26") (pin "2") (pinfunction "2_2") (pintype "passive"))
      (node (ref "R19") (pin "2") (pinfunction "2_2") (pintype "passive"))
      (node (ref "U5") (pin "2") (pinfunction "IN8P_2") (pintype "input"))
    )
    (net (code "57") (name "Net-(U5A-SRB1)") (class "Default")
      (node (ref "C19") (pin "1") (pinfunction "1_1") (pintype "passive"))
      (node (ref "C20") (pin "1") (pinfunction "1_1") (pintype "passive"))
      (node (ref "C21") (pin "1") (pinfunction "1_1") (pintype "passive"))
      (node (ref "C22") (pin "1") (pinfunction "1_1") (pintype "passive"))
      (node (ref "C23") (pin "1") (pinfunction "1_1") (pintype "passive"))
      (node (ref "C24") (pin "1") (pinfunction "1_1") (pintype "passive"))
      (node (ref "C25") (pin "1") (pinfunction "1_1") (pintype "passive"))
      (node (ref "C26") (pin "1") (pinfunction "1_1") (pintype "passive"))
      (node (ref "R33") (pin "2") (pinfunction "2_2") (pintype "passive"))
      (node (ref "U5") (pin "17") (pinfunction "SRB1_17") (pintype "input"))
    )
    (net (code "58") (name "Net-(U5A-SRB2)") (class "Default")
      (node (ref "R23") (pin "1") (pinfunction "1_1") (pintype "passive"))
      (node (ref "U5") (pin "18") (pinfunction "SRB2_18") (pintype "input"))
    )
    (net (code "59") (name "Net-(U5A-VCAP1)") (class "Default")
      (node (ref "C15_Vcap1") (pin "1") (pinfunction "1_1") (pintype "passive"))
      (node (ref "U5") (pin "28") (pinfunction "VCAP1_28") (pintype "passive"))
    )
    (net (code "60") (name "Net-(U5A-VCAP2)") (class "Default")
      (node (ref "C14_Vcap2") (pin "2") (pinfunction "2_2") (pintype "passive"))
      (node (ref "U5") (pin "30") (pinfunction "VCAP2_30") (pintype "passive"))
    )
    (net (code "61") (name "Net-(U5A-VCAP3)") (class "Default")
      (node (ref "C28") (pin "2") (pinfunction "2_2") (pintype "passive"))
      (node (ref "C29") (pin "2") (pinfunction "2_2") (pintype "passive"))
      (node (ref "U5") (pin "55") (pinfunction "VCAP3_55") (pintype "passive"))
    )
    (net (code "62") (name "Net-(U5A-VCAP4)") (class "Default")
      (node (ref "C16_Vcap4") (pin "2") (pinfunction "2_2") (pintype "passive"))
      (node (ref "U5") (pin "26") (pinfunction "VCAP4_26") (pintype "passive"))
    )
    (net (code "63") (name "Net-(U5A-VREFP)") (class "Default")
      (node (ref "C17") (pin "1") (pinfunction "1_1") (pintype "passive"))
      (node (ref "C18") (pin "2") (pinfunction "2_2") (pintype "passive"))
      (node (ref "U5") (pin "24") (pinfunction "VREFP_24") (pintype "passive"))
    )
    (net (code "64") (name "Net-(U5A-~{PWDN})") (class "Default")
      (node (ref "R10") (pin "2") (pinfunction "2_2") (pintype "passive"))
      (node (ref "U5") (pin "35") (pinfunction "~{PWDN}_35") (pintype "input"))
    )
    (net (code "65") (name "Net-(U5A-~{RESET})") (class "Default")
      (node (ref "R9") (pin "2") (pinfunction "2_2") (pintype "passive"))
      (node (ref "U5") (pin "36") (pinfunction "~{RESET}_36") (pintype "input"))
    )
    (net (code "66") (name "unconnected-(J1-A-Pad1)") (class "Default")
      (node (ref "J1-A") (pin "1") (pinfunction "1_1") (pintype "passive"))
    )
    (net (code "67") (name "unconnected-(J1-A-Pad3)") (class "Default")
      (node (ref "J1-A") (pin "3") (pinfunction "3_3") (pintype "passive"))
    )
    (net (code "68") (name "unconnected-(J1-A-Pad5)") (class "Default")
      (node (ref "J1-A") (pin "5") (pinfunction "5_5") (pintype "passive"))
    )
    (net (code "69") (name "unconnected-(J1-A-Pad8)") (class "Default")
      (node (ref "J1-A") (pin "8") (pinfunction "8_8") (pintype "passive"))
    )
    (net (code "70") (name "unconnected-(J1-A-Pad10)") (class "Default")
      (node (ref "J1-A") (pin "10") (pinfunction "10_10") (pintype "passive"))
    )
    (net (code "71") (name "unconnected-(J1-A-Pad12)") (class "Default")
      (node (ref "J1-A") (pin "12") (pinfunction "12_12") (pintype "passive"))
    )
    (net (code "72") (name "unconnected-(J1-A-Pad15)") (class "Default")
      (node (ref "J1-A") (pin "15") (pinfunction "15_15") (pintype "passive"))
    )
    (net (code "73") (name "unconnected-(J1-A-Pad16)") (class "Default")
      (node (ref "J1-A") (pin "16") (pinfunction "16_16") (pintype "passive"))
    )
    (net (code "74") (name "unconnected-(J1-A-Pad17)") (class "Default")
      (node (ref "J1-A") (pin "17") (pinfunction "17_17") (pintype "passive"))
    )
    (net (code "75") (name "unconnected-(J1-A-Pad18)") (class "Default")
      (node (ref "J1-A") (pin "18") (pinfunction "18_18") (pintype "passive"))
    )
    (net (code "76") (name "unconnected-(J1-A-Pad22)") (class "Default")
      (node (ref "J1-A") (pin "22") (pinfunction "22_22") (pintype "passive"))
    )
    (net (code "77") (name "unconnected-(J1-A-Pad26)") (class "Default")
      (node (ref "J1-A") (pin "26") (pinfunction "26_26") (pintype "passive"))
    )
    (net (code "78") (name "unconnected-(J1-A-Pad27)") (class "Default")
      (node (ref "J1-A") (pin "27") (pinfunction "27_27") (pintype "passive"))
    )
    (net (code "79") (name "unconnected-(J1-A-Pad28)") (class "Default")
      (node (ref "J1-A") (pin "28") (pinfunction "28_28") (pintype "passive"))
    )
    (net (code "80") (name "unconnected-(J1-A-Pad32)") (class "Default")
      (node (ref "J1-A") (pin "32") (pinfunction "32_32") (pintype "passive"))
    )
    (net (code "81") (name "unconnected-(J1-A-Pad36)") (class "Default")
      (node (ref "J1-A") (pin "36") (pinfunction "36_36") (pintype "passive"))
    )
    (net (code "82") (name "unconnected-(J1-A-Pad38)") (class "Default")
      (node (ref "J1-A") (pin "38") (pinfunction "38_38") (pintype "passive"))
    )
    (net (code "83") (name "unconnected-(J1-A-Pad40)") (class "Default")
      (node (ref "J1-A") (pin "40") (pinfunction "40_40") (pintype "passive"))
    )
    (net (code "84") (name "unconnected-(J1-B--Pad1)") (class "Default")
      (node (ref "J1-B-") (pin "1") (pinfunction "1_1") (pintype "passive"))
    )
    (net (code "85") (name "unconnected-(J1-B--Pad3)") (class "Default")
      (node (ref "J1-B-") (pin "3") (pinfunction "3_3") (pintype "passive"))
    )
    (net (code "86") (name "unconnected-(J1-B--Pad5)") (class "Default")
      (node (ref "J1-B-") (pin "5") (pinfunction "5_5") (pintype "passive"))
    )
    (net (code "87") (name "unconnected-(J1-B--Pad8)") (class "Default")
      (node (ref "J1-B-") (pin "8") (pinfunction "8_8") (pintype "passive"))
    )
    (net (code "88") (name "unconnected-(J1-B--Pad10)") (class "Default")
      (node (ref "J1-B-") (pin "10") (pinfunction "10_10") (pintype "passive"))
    )
    (net (code "89") (name "unconnected-(J1-B--Pad12)") (class "Default")
      (node (ref "J1-B-") (pin "12") (pinfunction "12_12") (pintype "passive"))
    )
    (net (code "90") (name "unconnected-(J1-B--Pad15)") (class "Default")
      (node (ref "J1-B-") (pin "15") (pinfunction "15_15") (pintype "passive"))
    )
    (net (code "91") (name "unconnected-(J1-B--Pad16)") (class "Default")
      (node (ref "J1-B-") (pin "16") (pinfunction "16_16") (pintype "passive"))
    )
    (net (code "92") (name "unconnected-(J1-B--Pad17)") (class "Default")
      (node (ref "J1-B-") (pin "17") (pinfunction "17_17") (pintype "passive"))
    )
    (net (code "93") (name "unconnected-(J1-B--Pad18)") (class "Default")
      (node (ref "J1-B-") (pin "18") (pinfunction "18_18") (pintype "passive"))
    )
    (net (code "94") (name "unconnected-(J1-B--Pad22)") (class "Default")
      (node (ref "J1-B-") (pin "22") (pinfunction "22_22") (pintype "passive"))
    )
    (net (code "95") (name "unconnected-(J1-B--Pad26)") (class "Default")
      (node (ref "J1-B-") (pin "26") (pinfunction "26_26") (pintype "passive"))
    )
    (net (code "96") (name "unconnected-(J1-B--Pad27)") (class "Default")
      (node (ref "J1-B-") (pin "27") (pinfunction "27_27") (pintype "passive"))
    )
    (net (code "97") (name "unconnected-(J1-B--Pad28)") (class "Default")
      (node (ref "J1-B-") (pin "28") (pinfunction "28_28") (pintype "passive"))
    )
    (net (code "98") (name "unconnected-(J1-B--Pad32)") (class "Default")
      (node (ref "J1-B-") (pin "32") (pinfunction "32_32") (pintype "passive"))
    )
    (net (code "99") (name "unconnected-(J1-B--Pad36)") (class "Default")
      (node (ref "J1-B-") (pin "36") (pinfunction "36_36") (pintype "passive"))
    )
    (net (code "100") (name "unconnected-(J1-B--Pad38)") (class "Default")
      (node (ref "J1-B-") (pin "38") (pinfunction "38_38") (pintype "passive"))
    )
    (net (code "101") (name "unconnected-(J1-B--Pad40)") (class "Default")
      (node (ref "J1-B-") (pin "40") (pinfunction "40_40") (pintype "passive"))
    )
    (net (code "102") (name "unconnected-(J1-C--Pad1)") (class "Default")
      (node (ref "J1-C-") (pin "1") (pinfunction "1_1") (pintype "passive"))
    )
    (net (code "103") (name "unconnected-(J1-C--Pad3)") (class "Default")
      (node (ref "J1-C-") (pin "3") (pinfunction "3_3") (pintype "passive"))
    )
    (net (code "104") (name "unconnected-(J1-C--Pad5)") (class "Default")
      (node (ref "J1-C-") (pin "5") (pinfunction "5_5") (pintype "passive"))
    )
    (net (code "105") (name "unconnected-(J1-C--Pad8)") (class "Default")
      (node (ref "J1-C-") (pin "8") (pinfunction "8_8") (pintype "passive"))
    )
    (net (code "106") (name "unconnected-(J1-C--Pad10)") (class "Default")
      (node (ref "J1-C-") (pin "10") (pinfunction "10_10") (pintype "passive"))
    )
    (net (code "107") (name "unconnected-(J1-C--Pad12)") (class "Default")
      (node (ref "J1-C-") (pin "12") (pinfunction "12_12") (pintype "passive"))
    )
    (net (code "108") (name "unconnected-(J1-C--Pad15)") (class "Default")
      (node (ref "J1-C-") (pin "15") (pinfunction "15_15") (pintype "passive"))
    )
    (net (code "109") (name "unconnected-(J1-C--Pad16)") (class "Default")
      (node (ref "J1-C-") (pin "16") (pinfunction "16_16") (pintype "passive"))
    )
    (net (code "110") (name "unconnected-(J1-C--Pad17)") (class "Default")
      (node (ref "J1-C-") (pin "17") (pinfunction "17_17") (pintype "passive"))
    )
    (net (code "111") (name "unconnected-(J1-C--Pad18)") (class "Default")
      (node (ref "J1-C-") (pin "18") (pinfunction "18_18") (pintype "passive"))
    )
    (net (code "112") (name "unconnected-(J1-C--Pad22)") (class "Default")
      (node (ref "J1-C-") (pin "22") (pinfunction "22_22") (pintype "passive"))
    )
    (net (code "113") (name "unconnected-(J1-C--Pad26)") (class "Default")
      (node (ref "J1-C-") (pin "26") (pinfunction "26_26") (pintype "passive"))
    )
    (net (code "114") (name "unconnected-(J1-C--Pad27)") (class "Default")
      (node (ref "J1-C-") (pin "27") (pinfunction "27_27") (pintype "passive"))
    )
    (net (code "115") (name "unconnected-(J1-C--Pad28)") (class "Default")
      (node (ref "J1-C-") (pin "28") (pinfunction "28_28") (pintype "passive"))
    )
    (net (code "116") (name "unconnected-(J1-C--Pad32)") (class "Default")
      (node (ref "J1-C-") (pin "32") (pinfunction "32_32") (pintype "passive"))
    )
    (net (code "117") (name "unconnected-(J1-C--Pad36)") (class "Default")
      (node (ref "J1-C-") (pin "36") (pinfunction "36_36") (pintype "passive"))
    )
    (net (code "118") (name "unconnected-(J1-C--Pad38)") (class "Default")
      (node (ref "J1-C-") (pin "38") (pinfunction "38_38") (pintype "passive"))
    )
    (net (code "119") (name "unconnected-(J1-C--Pad40)") (class "Default")
      (node (ref "J1-C-") (pin "40") (pinfunction "40_40") (pintype "passive"))
    )
    (net (code "120") (name "unconnected-(M1-PadS)") (class "Default")
      (node (ref "M1") (pin "S") (pinfunction "S_S") (pintype "passive"))
    )
    (net (code "121") (name "unconnected-(M2-PadS)") (class "Default")
      (node (ref "M2") (pin "S") (pinfunction "S_S") (pintype "passive"))
    )
    (net (code "122") (name "unconnected-(M3-PadS)") (class "Default")
      (node (ref "M3") (pin "S") (pinfunction "S_S") (pintype "passive"))
    )
    (net (code "123") (name "unconnected-(M4-PadS)") (class "Default")
      (node (ref "M4") (pin "S") (pinfunction "S_S") (pintype "passive"))
    )
    (net (code "124") (name "unconnected-(U1-PG-Pad4)") (class "Default")
      (node (ref "U1") (pin "4") (pinfunction "PG_4") (pintype "open_collector"))
    )
    (net (code "125") (name "unconnected-(U2-PG-Pad4)") (class "Default")
      (node (ref "U2") (pin "4") (pinfunction "PG_4") (pintype "open_collector"))
    )
    (net (code "126") (name "unconnected-(U3-FC-Pad1)") (class "Default")
      (node (ref "U3") (pin "1") (pinfunction "FC_1") (pintype "input"))
    )
    (net (code "127") (name "unconnected-(U3-OSC-Pad7)") (class "Default")
      (node (ref "U3") (pin "7") (pinfunction "OSC_7") (pintype "input"))
    )
    (net (code "128") (name "unconnected-(U4-ILIM-Pad6)") (class "Default")
      (node (ref "U4") (pin "6") (pinfunction "ILIM_6") (pintype "input"))
    )
    (net (code "129") (name "unconnected-(U4-PG-Pad4)") (class "Default")
      (node (ref "U4") (pin "4") (pinfunction "PG_4") (pintype "output"))
    )
    (net (code "130") (name "unconnected-(U4-VIOC-Pad7)") (class "Default")
      (node (ref "U4") (pin "7") (pinfunction "VIOC_7") (pintype "bidirectional"))
    )
    (net (code "131") (name "unconnected-(U5A-CLK-Pad37)") (class "Default")
      (node (ref "U5") (pin "37") (pinfunction "CLK_37") (pintype "bidirectional"))
    )
    (net (code "132") (name "unconnected-(U5A-IN1N-Pad15)") (class "Default")
      (node (ref "U5") (pin "15") (pinfunction "IN1N_15") (pintype "input"))
    )
    (net (code "133") (name "unconnected-(U5A-IN2N-Pad13)") (class "Default")
      (node (ref "U5") (pin "13") (pinfunction "IN2N_13") (pintype "input"))
    )
    (net (code "134") (name "unconnected-(U5A-IN3N-Pad11)") (class "Default")
      (node (ref "U5") (pin "11") (pinfunction "IN3N_11") (pintype "input"))
    )
    (net (code "135") (name "unconnected-(U5A-IN4N-Pad9)") (class "Default")
      (node (ref "U5") (pin "9") (pinfunction "IN4N_9") (pintype "input"))
    )
    (net (code "136") (name "unconnected-(U5A-IN5N-Pad7)") (class "Default")
      (node (ref "U5") (pin "7") (pinfunction "IN5N_7") (pintype "input"))
    )
    (net (code "137") (name "unconnected-(U5A-IN6N-Pad5)") (class "Default")
      (node (ref "U5") (pin "5") (pinfunction "IN6N_5") (pintype "input"))
    )
    (net (code "138") (name "unconnected-(U5A-IN7N-Pad3)") (class "Default")
      (node (ref "U5") (pin "3") (pinfunction "IN7N_3") (pintype "input"))
    )
    (net (code "139") (name "unconnected-(U5A-IN8N-Pad1)") (class "Default")
      (node (ref "U5") (pin "1") (pinfunction "IN8N_1") (pintype "input"))
    )
    (net (code "140") (name "unconnected-(U5A-NC-Pad27)") (class "Default")
      (node (ref "U5") (pin "27") (pinfunction "NC_27") (pintype "passive"))
    )
    (net (code "141") (name "unconnected-(U5A-NC-Pad29)") (class "Default")
      (node (ref "U5") (pin "29") (pinfunction "NC_29") (pintype "passive"))
    )
    (net (code "142") (name "unconnected-(U5A-RESERVED-Pad64)") (class "Default")
      (node (ref "U5") (pin "64") (pinfunction "RESERVED_64") (pintype "passive"))
    )
  )
)
